# REV1.net
KiCad netlist of a schematic drawn in EAGLE
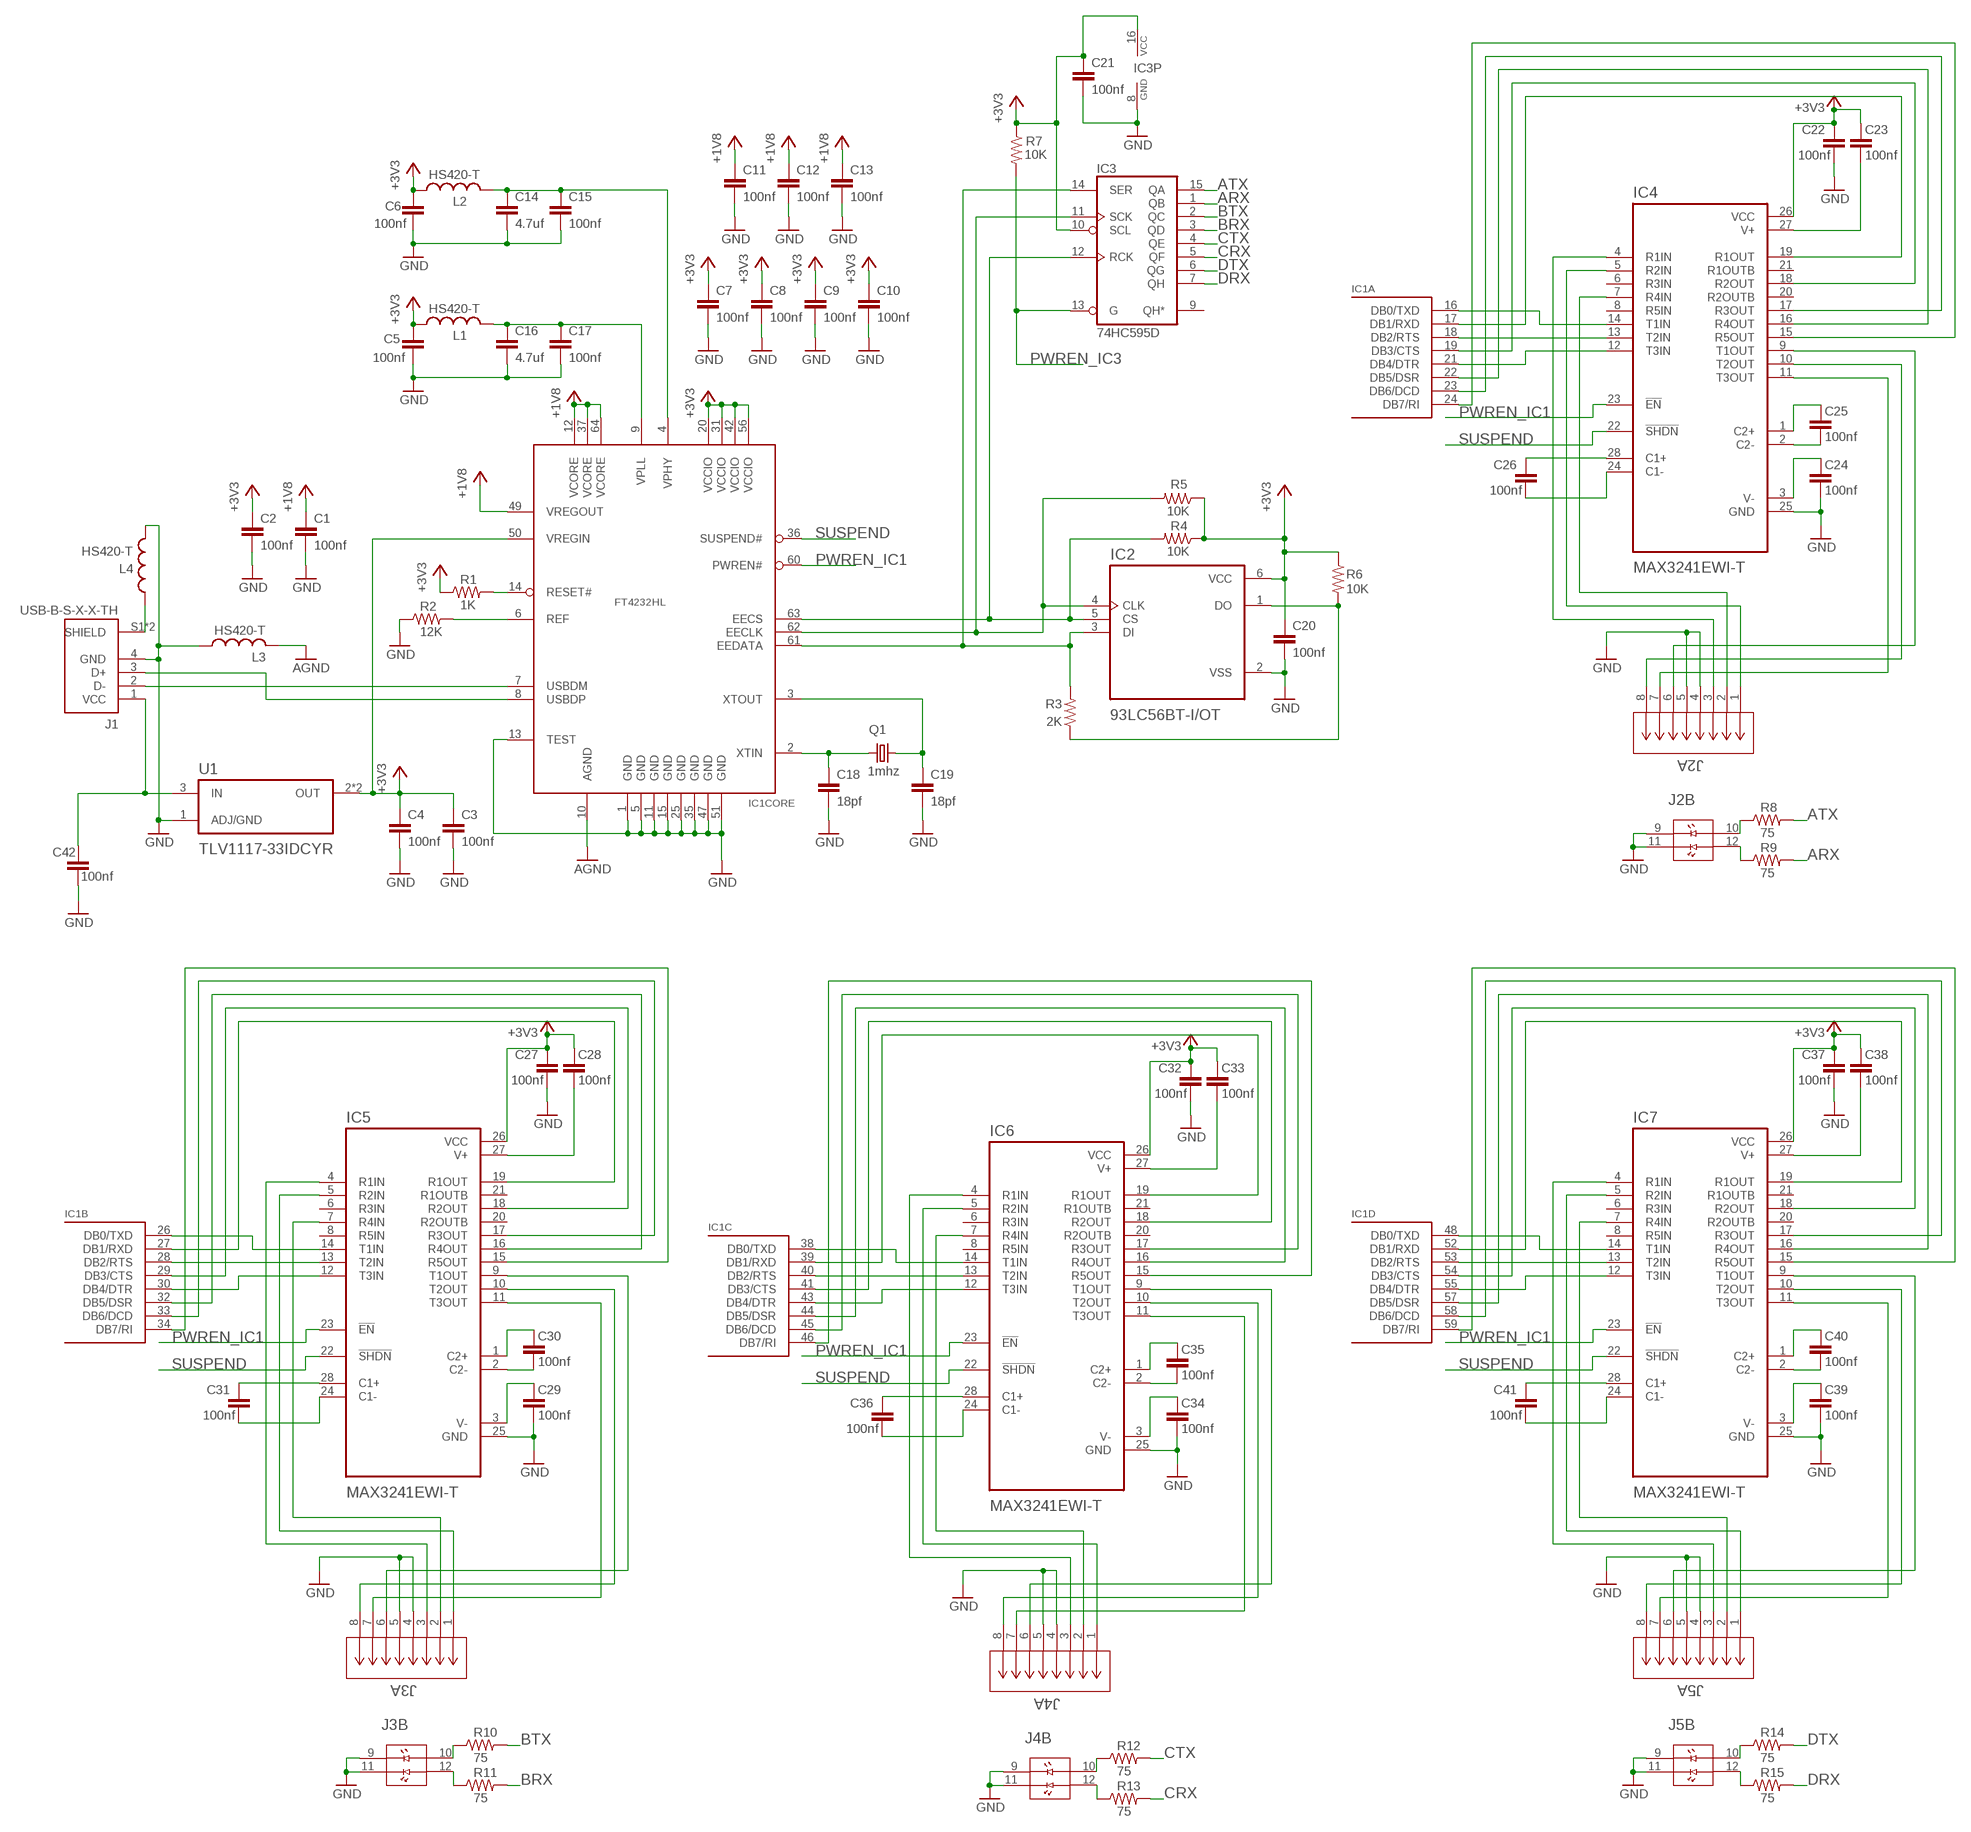
[diagram p0: schematic, sheet 1]

(export (version "E")
  (design (tool "Eeschema 10.0.6"))
  (components
    (comp (ref "C1")
      (value "100nf")
      (footprint "eagle-import:C0603")
      (libsource (lib "eagle-import") (part "C-EUC0603"))
    )
    (comp (ref "C2")
      (value "100nf")
      (footprint "eagle-import:C0603")
      (libsource (lib "eagle-import") (part "C-EUC0603"))
    )
    (comp (ref "C3")
      (value "100nf")
      (footprint "eagle-import:C0603")
      (libsource (lib "eagle-import") (part "C-EUC0603"))
    )
    (comp (ref "C4")
      (value "100nf")
      (footprint "eagle-import:C0603")
      (libsource (lib "eagle-import") (part "C-EUC0603"))
    )
    (comp (ref "C5")
      (value "100nf")
      (footprint "eagle-import:C0603")
      (libsource (lib "eagle-import") (part "C-EUC0603"))
    )
    (comp (ref "C6")
      (value "100nf")
      (footprint "eagle-import:C0603")
      (libsource (lib "eagle-import") (part "C-EUC0603"))
    )
    (comp (ref "C7")
      (value "100nf")
      (footprint "eagle-import:C0603")
      (libsource (lib "eagle-import") (part "C-EUC0603"))
    )
    (comp (ref "C8")
      (value "100nf")
      (footprint "eagle-import:C0603")
      (libsource (lib "eagle-import") (part "C-EUC0603"))
    )
    (comp (ref "C9")
      (value "100nf")
      (footprint "eagle-import:C0603")
      (libsource (lib "eagle-import") (part "C-EUC0603"))
    )
    (comp (ref "C10")
      (value "100nf")
      (footprint "eagle-import:C0603")
      (libsource (lib "eagle-import") (part "C-EUC0603"))
    )
    (comp (ref "C11")
      (value "100nf")
      (footprint "eagle-import:C0603")
      (libsource (lib "eagle-import") (part "C-EUC0603"))
    )
    (comp (ref "C12")
      (value "100nf")
      (footprint "eagle-import:C0603")
      (libsource (lib "eagle-import") (part "C-EUC0603"))
    )
    (comp (ref "C13")
      (value "100nf")
      (footprint "eagle-import:C0603")
      (libsource (lib "eagle-import") (part "C-EUC0603"))
    )
    (comp (ref "C14")
      (value "4.7uf")
      (footprint "eagle-import:C0603")
      (libsource (lib "eagle-import") (part "C-EUC0603"))
    )
    (comp (ref "C15")
      (value "100nf")
      (footprint "eagle-import:C0603")
      (libsource (lib "eagle-import") (part "C-EUC0603"))
    )
    (comp (ref "C16")
      (value "4.7uf")
      (footprint "eagle-import:C0603")
      (libsource (lib "eagle-import") (part "C-EUC0603"))
    )
    (comp (ref "C17")
      (value "100nf")
      (footprint "eagle-import:C0603")
      (libsource (lib "eagle-import") (part "C-EUC0603"))
    )
    (comp (ref "C18")
      (value "18pf")
      (footprint "eagle-import:C0603")
      (libsource (lib "eagle-import") (part "C-EUC0603"))
    )
    (comp (ref "C19")
      (value "18pf")
      (footprint "eagle-import:C0603")
      (libsource (lib "eagle-import") (part "C-EUC0603"))
    )
    (comp (ref "C20")
      (value "100nf")
      (footprint "eagle-import:C0603")
      (libsource (lib "eagle-import") (part "C-EUC0603"))
    )
    (comp (ref "C21")
      (value "100nf")
      (footprint "eagle-import:C0603")
      (libsource (lib "eagle-import") (part "C-EUC0603"))
    )
    (comp (ref "C22")
      (value "100nf")
      (footprint "eagle-import:C0603")
      (libsource (lib "eagle-import") (part "C-EUC0603"))
    )
    (comp (ref "C23")
      (value "100nf")
      (footprint "eagle-import:C0603")
      (libsource (lib "eagle-import") (part "C-EUC0603"))
    )
    (comp (ref "C24")
      (value "100nf")
      (footprint "eagle-import:C0603")
      (libsource (lib "eagle-import") (part "C-EUC0603"))
    )
    (comp (ref "C25")
      (value "100nf")
      (footprint "eagle-import:C0603")
      (libsource (lib "eagle-import") (part "C-EUC0603"))
    )
    (comp (ref "C26")
      (value "100nf")
      (footprint "eagle-import:C0603")
      (libsource (lib "eagle-import") (part "C-EUC0603"))
    )
    (comp (ref "C27")
      (value "100nf")
      (footprint "eagle-import:C0603")
      (libsource (lib "eagle-import") (part "C-EUC0603"))
    )
    (comp (ref "C28")
      (value "100nf")
      (footprint "eagle-import:C0603")
      (libsource (lib "eagle-import") (part "C-EUC0603"))
    )
    (comp (ref "C29")
      (value "100nf")
      (footprint "eagle-import:C0603")
      (libsource (lib "eagle-import") (part "C-EUC0603"))
    )
    (comp (ref "C30")
      (value "100nf")
      (footprint "eagle-import:C0603")
      (libsource (lib "eagle-import") (part "C-EUC0603"))
    )
    (comp (ref "C31")
      (value "100nf")
      (footprint "eagle-import:C0603")
      (libsource (lib "eagle-import") (part "C-EUC0603"))
    )
    (comp (ref "C32")
      (value "100nf")
      (footprint "eagle-import:C0603")
      (libsource (lib "eagle-import") (part "C-EUC0603"))
    )
    (comp (ref "C33")
      (value "100nf")
      (footprint "eagle-import:C0603")
      (libsource (lib "eagle-import") (part "C-EUC0603"))
    )
    (comp (ref "C34")
      (value "100nf")
      (footprint "eagle-import:C0603")
      (libsource (lib "eagle-import") (part "C-EUC0603"))
    )
    (comp (ref "C35")
      (value "100nf")
      (footprint "eagle-import:C0603")
      (libsource (lib "eagle-import") (part "C-EUC0603"))
    )
    (comp (ref "C36")
      (value "100nf")
      (footprint "eagle-import:C0603")
      (libsource (lib "eagle-import") (part "C-EUC0603"))
    )
    (comp (ref "C37")
      (value "100nf")
      (footprint "eagle-import:C0603")
      (libsource (lib "eagle-import") (part "C-EUC0603"))
    )
    (comp (ref "C38")
      (value "100nf")
      (footprint "eagle-import:C0603")
      (libsource (lib "eagle-import") (part "C-EUC0603"))
    )
    (comp (ref "C39")
      (value "100nf")
      (footprint "eagle-import:C0603")
      (libsource (lib "eagle-import") (part "C-EUC0603"))
    )
    (comp (ref "C40")
      (value "100nf")
      (footprint "eagle-import:C0603")
      (libsource (lib "eagle-import") (part "C-EUC0603"))
    )
    (comp (ref "C41")
      (value "100nf")
      (footprint "eagle-import:C0603")
      (libsource (lib "eagle-import") (part "C-EUC0603"))
    )
    (comp (ref "C42")
      (value "100nf")
      (footprint "eagle-import:C0603")
      (libsource (lib "eagle-import") (part "C-EUC0603"))
    )
    (comp (ref "IC1")
      (value "FT4232HL")
      (footprint "eagle-import:LQFP64")
      (libsource (lib "eagle-import") (part "FT4232HL"))
    )
    (comp (ref "IC2")
      (value "93LC56BT-I/OT")
      (footprint "eagle-import:SOT95P280X145-6N")
      (fields (field (name "MF") "Microchip Technology"))
      (libsource (lib "eagle-import") (part "93LC56BT-I/OT"))
    )
    (comp (ref "IC3")
      (value "74HC595D")
      (footprint "eagle-import:SO16")
      (libsource (lib "eagle-import") (part "74595DHC"))
    )
    (comp (ref "IC4")
      (value "MAX3241EWI-T")
      (footprint "eagle-import:SOIC127P1032X265-28N")
      (fields
        (field (name "DIGI-KEY_PART_NUMBER") "MAX3241EWI+T-ND")
        (field (name "MF") "Maxim Integrated")
        (field (name "MP") "MAX3241EWI+")
      )
      (libsource (lib "eagle-import") (part "MAX3241EWI-T"))
    )
    (comp (ref "IC5")
      (value "MAX3241EWI-T")
      (footprint "eagle-import:SOIC127P1032X265-28N")
      (fields
        (field (name "DIGI-KEY_PART_NUMBER") "MAX3241EWI+T-ND")
        (field (name "MF") "Maxim Integrated")
        (field (name "MP") "MAX3241EWI+")
      )
      (libsource (lib "eagle-import") (part "MAX3241EWI-T"))
    )
    (comp (ref "IC6")
      (value "MAX3241EWI-T")
      (footprint "eagle-import:SOIC127P1032X265-28N")
      (fields
        (field (name "DIGI-KEY_PART_NUMBER") "MAX3241EWI+T-ND")
        (field (name "MF") "Maxim Integrated")
        (field (name "MP") "MAX3241EWI+")
      )
      (libsource (lib "eagle-import") (part "MAX3241EWI-T"))
    )
    (comp (ref "IC7")
      (value "MAX3241EWI-T")
      (footprint "eagle-import:SOIC127P1032X265-28N")
      (fields
        (field (name "DIGI-KEY_PART_NUMBER") "MAX3241EWI+T-ND")
        (field (name "MF") "Maxim Integrated")
        (field (name "MP") "MAX3241EWI+")
      )
      (libsource (lib "eagle-import") (part "MAX3241EWI-T"))
    )
    (comp (ref "J1")
      (value "USB-B-S-X-X-TH")
      (footprint "eagle-import:SAMTEC_USB-B-S-X-X-TH")
      (fields (field (name "MF") "Samtec") (field (name "MP") "USB-B-S-S-B-TH"))
      (libsource (lib "eagle-import") (part "USB-B-S-X-X-TH"))
    )
    (comp (ref "J2")
      (value "RJHSE-5384")
      (footprint "eagle-import:RJHSE-5384_AMP")
      (fields (field (name "COPYRIGHT") "Copyright (C) 2018 Accelerated Designs. All rights reserved"))
      (libsource (lib "eagle-import") (part "RJHSE-5384"))
    )
    (comp (ref "J3")
      (value "RJHSE-5384")
      (footprint "eagle-import:RJHSE-5384_AMP")
      (fields (field (name "COPYRIGHT") "Copyright (C) 2018 Accelerated Designs. All rights reserved"))
      (libsource (lib "eagle-import") (part "RJHSE-5384"))
    )
    (comp (ref "J4")
      (value "RJHSE-5384")
      (footprint "eagle-import:RJHSE-5384_AMP")
      (fields (field (name "COPYRIGHT") "Copyright (C) 2018 Accelerated Designs. All rights reserved"))
      (libsource (lib "eagle-import") (part "RJHSE-5384"))
    )
    (comp (ref "J5")
      (value "RJHSE-5384")
      (footprint "eagle-import:RJHSE-5384_AMP")
      (fields (field (name "COPYRIGHT") "Copyright (C) 2018 Accelerated Designs. All rights reserved"))
      (libsource (lib "eagle-import") (part "RJHSE-5384"))
    )
    (comp (ref "L1")
      (value "HS420-T")
      (footprint "eagle-import:L2012C")
      (libsource (lib "eagle-import") (part "L-USL2012C"))
    )
    (comp (ref "L2")
      (value "HS420-T")
      (footprint "eagle-import:L2012C")
      (libsource (lib "eagle-import") (part "L-USL2012C"))
    )
    (comp (ref "L3")
      (value "HS420-T")
      (footprint "eagle-import:L2012C")
      (libsource (lib "eagle-import") (part "L-USL2012C"))
    )
    (comp (ref "L4")
      (value "HS420-T")
      (footprint "eagle-import:L2012C")
      (libsource (lib "eagle-import") (part "L-USL2012C"))
    )
    (comp (ref "Q1")
      (value "1mhz")
      (footprint "eagle-import:HC49_S")
      (libsource (lib "eagle-import") (part "CRYSTALHC49S"))
    )
    (comp (ref "R1")
      (value "1K")
      (footprint "eagle-import:R0805")
      (libsource (lib "eagle-import") (part "R-US_R0805"))
    )
    (comp (ref "R2")
      (value "12K")
      (footprint "eagle-import:R0805")
      (libsource (lib "eagle-import") (part "R-US_R0805"))
    )
    (comp (ref "R3")
      (value "2K")
      (footprint "eagle-import:R0805")
      (libsource (lib "eagle-import") (part "R-US_R0805"))
    )
    (comp (ref "R4")
      (value "10K")
      (footprint "eagle-import:R0805")
      (libsource (lib "eagle-import") (part "R-US_R0805"))
    )
    (comp (ref "R5")
      (value "10K")
      (footprint "eagle-import:R0805")
      (libsource (lib "eagle-import") (part "R-US_R0805"))
    )
    (comp (ref "R6")
      (value "10K")
      (footprint "eagle-import:R0805")
      (libsource (lib "eagle-import") (part "R-US_R0805"))
    )
    (comp (ref "R7")
      (value "10K")
      (footprint "eagle-import:R0805")
      (libsource (lib "eagle-import") (part "R-US_R0805"))
    )
    (comp (ref "R8")
      (value "75")
      (footprint "eagle-import:R0805")
      (libsource (lib "eagle-import") (part "R-US_R0805"))
    )
    (comp (ref "R9")
      (value "75")
      (footprint "eagle-import:R0805")
      (libsource (lib "eagle-import") (part "R-US_R0805"))
    )
    (comp (ref "R10")
      (value "75")
      (footprint "eagle-import:R0805")
      (libsource (lib "eagle-import") (part "R-US_R0805"))
    )
    (comp (ref "R11")
      (value "75")
      (footprint "eagle-import:R0805")
      (libsource (lib "eagle-import") (part "R-US_R0805"))
    )
    (comp (ref "R12")
      (value "75")
      (footprint "eagle-import:R0805")
      (libsource (lib "eagle-import") (part "R-US_R0805"))
    )
    (comp (ref "R13")
      (value "75")
      (footprint "eagle-import:R0805")
      (libsource (lib "eagle-import") (part "R-US_R0805"))
    )
    (comp (ref "R14")
      (value "75")
      (footprint "eagle-import:R0805")
      (libsource (lib "eagle-import") (part "R-US_R0805"))
    )
    (comp (ref "R15")
      (value "75")
      (footprint "eagle-import:R0805")
      (libsource (lib "eagle-import") (part "R-US_R0805"))
    )
    (comp (ref "U1")
      (value "TLV1117-33IDCYR")
      (footprint "eagle-import:SOT230P700X180-4N")
      (fields (field (name "DIGI-KEY_PART_NUMBER") "296-21113-1-ND") (field (name "MF") "Texas Instruments"))
      (libsource (lib "eagle-import") (part "TLV1117-33IDCYR"))
    )
  )
  (nets
    (net (code "1") (name "+1V8") (class "Default")
      (node (ref "C1") (pin "1") (pinfunction "1_1") (pintype "passive"))
      (node (ref "C11") (pin "1") (pinfunction "1_1") (pintype "passive"))
      (node (ref "C12") (pin "1") (pinfunction "1_1") (pintype "passive"))
      (node (ref "C13") (pin "1") (pinfunction "1_1") (pintype "passive"))
      (node (ref "IC1") (pin "12") (pinfunction "VCORE_12") (pintype "power_in"))
      (node (ref "IC1") (pin "37") (pinfunction "VCORE_37") (pintype "power_in"))
      (node (ref "IC1") (pin "49") (pinfunction "VREGOUT_49") (pintype "output"))
      (node (ref "IC1") (pin "64") (pinfunction "VCORE_64") (pintype "power_in"))
    )
    (net (code "2") (name "+3V3") (class "Default")
      (node (ref "C10") (pin "1") (pinfunction "1_1") (pintype "passive"))
      (node (ref "C2") (pin "1") (pinfunction "1_1") (pintype "passive"))
      (node (ref "C20") (pin "1") (pinfunction "1_1") (pintype "passive"))
      (node (ref "C21") (pin "1") (pinfunction "1_1") (pintype "passive"))
      (node (ref "C22") (pin "1") (pinfunction "1_1") (pintype "passive"))
      (node (ref "C23") (pin "1") (pinfunction "1_1") (pintype "passive"))
      (node (ref "C27") (pin "1") (pinfunction "1_1") (pintype "passive"))
      (node (ref "C28") (pin "1") (pinfunction "1_1") (pintype "passive"))
      (node (ref "C3") (pin "1") (pinfunction "1_1") (pintype "passive"))
      (node (ref "C32") (pin "1") (pinfunction "1_1") (pintype "passive"))
      (node (ref "C33") (pin "1") (pinfunction "1_1") (pintype "passive"))
      (node (ref "C37") (pin "1") (pinfunction "1_1") (pintype "passive"))
      (node (ref "C38") (pin "1") (pinfunction "1_1") (pintype "passive"))
      (node (ref "C4") (pin "1") (pinfunction "1_1") (pintype "passive"))
      (node (ref "C5") (pin "1") (pinfunction "1_1") (pintype "passive"))
      (node (ref "C6") (pin "1") (pinfunction "1_1") (pintype "passive"))
      (node (ref "C7") (pin "1") (pinfunction "1_1") (pintype "passive"))
      (node (ref "C8") (pin "1") (pinfunction "1_1") (pintype "passive"))
      (node (ref "C9") (pin "1") (pinfunction "1_1") (pintype "passive"))
      (node (ref "IC1") (pin "20") (pinfunction "VCCIO_20") (pintype "power_in"))
      (node (ref "IC1") (pin "31") (pinfunction "VCCIO_31") (pintype "power_in"))
      (node (ref "IC1") (pin "42") (pinfunction "VCCIO_42") (pintype "power_in"))
      (node (ref "IC1") (pin "50") (pinfunction "VREGIN_50") (pintype "bidirectional"))
      (node (ref "IC1") (pin "56") (pinfunction "VCCIO_56") (pintype "power_in"))
      (node (ref "IC2") (pin "6") (pinfunction "VCC_6") (pintype "power_in"))
      (node (ref "IC3") (pin "10") (pinfunction "SCL_10") (pintype "input"))
      (node (ref "IC3") (pin "16") (pinfunction "VCC_16") (pintype "power_in"))
      (node (ref "IC4") (pin "26") (pinfunction "VCC_26") (pintype "power_in"))
      (node (ref "IC5") (pin "26") (pinfunction "VCC_26") (pintype "power_in"))
      (node (ref "IC6") (pin "26") (pinfunction "VCC_26") (pintype "power_in"))
      (node (ref "IC7") (pin "26") (pinfunction "VCC_26") (pintype "power_in"))
      (node (ref "L1") (pin "1") (pinfunction "1_1") (pintype "passive"))
      (node (ref "L2") (pin "1") (pinfunction "1_1") (pintype "passive"))
      (node (ref "R1") (pin "1") (pinfunction "1_1") (pintype "passive"))
      (node (ref "R4") (pin "1") (pinfunction "1_1") (pintype "passive"))
      (node (ref "R5") (pin "1") (pinfunction "1_1") (pintype "passive"))
      (node (ref "R6") (pin "1") (pinfunction "1_1") (pintype "passive"))
      (node (ref "R7") (pin "1") (pinfunction "1_1") (pintype "passive"))
      (node (ref "U1") (pin "2") (pinfunction "OUT_2") (pintype "output"))
      (node (ref "U1") (pin "4") (pinfunction "OUT_4") (pintype "output"))
    )
    (net (code "3") (name "/ARX") (class "Default")
      (node (ref "IC3") (pin "1") (pinfunction "QB_1") (pintype "tri_state"))
      (node (ref "R9") (pin "2") (pinfunction "2_2") (pintype "passive"))
    )
    (net (code "4") (name "/ATX") (class "Default")
      (node (ref "IC3") (pin "15") (pinfunction "QA_15") (pintype "tri_state"))
      (node (ref "R8") (pin "2") (pinfunction "2_2") (pintype "passive"))
    )
    (net (code "5") (name "/BRX") (class "Default")
      (node (ref "IC3") (pin "3") (pinfunction "QD_3") (pintype "tri_state"))
      (node (ref "R11") (pin "2") (pinfunction "2_2") (pintype "passive"))
    )
    (net (code "6") (name "/BTX") (class "Default")
      (node (ref "IC3") (pin "2") (pinfunction "QC_2") (pintype "tri_state"))
      (node (ref "R10") (pin "2") (pinfunction "2_2") (pintype "passive"))
    )
    (net (code "7") (name "/CRX") (class "Default")
      (node (ref "IC3") (pin "5") (pinfunction "QF_5") (pintype "tri_state"))
      (node (ref "R13") (pin "2") (pinfunction "2_2") (pintype "passive"))
    )
    (net (code "8") (name "/CTX") (class "Default")
      (node (ref "IC3") (pin "4") (pinfunction "QE_4") (pintype "tri_state"))
      (node (ref "R12") (pin "2") (pinfunction "2_2") (pintype "passive"))
    )
    (net (code "9") (name "/DRX") (class "Default")
      (node (ref "IC3") (pin "7") (pinfunction "QH_7") (pintype "tri_state"))
      (node (ref "R15") (pin "2") (pinfunction "2_2") (pintype "passive"))
    )
    (net (code "10") (name "/DTX") (class "Default")
      (node (ref "IC3") (pin "6") (pinfunction "QG_6") (pintype "tri_state"))
      (node (ref "R14") (pin "2") (pinfunction "2_2") (pintype "passive"))
    )
    (net (code "11") (name "/PWREN_IC1") (class "Default")
      (node (ref "IC1") (pin "60") (pinfunction "PWREN#_60") (pintype "output"))
      (node (ref "IC4") (pin "23") (pinfunction "~{EN}_23") (pintype "bidirectional"))
      (node (ref "IC5") (pin "23") (pinfunction "~{EN}_23") (pintype "bidirectional"))
      (node (ref "IC6") (pin "23") (pinfunction "~{EN}_23") (pintype "bidirectional"))
      (node (ref "IC7") (pin "23") (pinfunction "~{EN}_23") (pintype "bidirectional"))
    )
    (net (code "12") (name "/PWREN_IC3") (class "Default")
      (node (ref "IC3") (pin "13") (pinfunction "G_13") (pintype "input"))
      (node (ref "R7") (pin "2") (pinfunction "2_2") (pintype "passive"))
    )
    (net (code "13") (name "/SUSPEND") (class "Default")
      (node (ref "IC1") (pin "36") (pinfunction "SUSPEND#_36") (pintype "output"))
      (node (ref "IC4") (pin "22") (pinfunction "~{SHDN}_22") (pintype "bidirectional"))
      (node (ref "IC5") (pin "22") (pinfunction "~{SHDN}_22") (pintype "bidirectional"))
      (node (ref "IC6") (pin "22") (pinfunction "~{SHDN}_22") (pintype "bidirectional"))
      (node (ref "IC7") (pin "22") (pinfunction "~{SHDN}_22") (pintype "bidirectional"))
    )
    (net (code "14") (name "AGND") (class "Default")
      (node (ref "IC1") (pin "10") (pinfunction "AGND_10") (pintype "power_in"))
      (node (ref "L3") (pin "2") (pinfunction "2_2") (pintype "passive"))
    )
    (net (code "15") (name "GND") (class "Default")
      (node (ref "C1") (pin "2") (pinfunction "2_2") (pintype "passive"))
      (node (ref "C10") (pin "2") (pinfunction "2_2") (pintype "passive"))
      (node (ref "C11") (pin "2") (pinfunction "2_2") (pintype "passive"))
      (node (ref "C12") (pin "2") (pinfunction "2_2") (pintype "passive"))
      (node (ref "C13") (pin "2") (pinfunction "2_2") (pintype "passive"))
      (node (ref "C14") (pin "2") (pinfunction "2_2") (pintype "passive"))
      (node (ref "C15") (pin "2") (pinfunction "2_2") (pintype "passive"))
      (node (ref "C16") (pin "2") (pinfunction "2_2") (pintype "passive"))
      (node (ref "C17") (pin "2") (pinfunction "2_2") (pintype "passive"))
      (node (ref "C18") (pin "2") (pinfunction "2_2") (pintype "passive"))
      (node (ref "C19") (pin "2") (pinfunction "2_2") (pintype "passive"))
      (node (ref "C2") (pin "2") (pinfunction "2_2") (pintype "passive"))
      (node (ref "C20") (pin "2") (pinfunction "2_2") (pintype "passive"))
      (node (ref "C21") (pin "2") (pinfunction "2_2") (pintype "passive"))
      (node (ref "C22") (pin "2") (pinfunction "2_2") (pintype "passive"))
      (node (ref "C24") (pin "2") (pinfunction "2_2") (pintype "passive"))
      (node (ref "C27") (pin "2") (pinfunction "2_2") (pintype "passive"))
      (node (ref "C29") (pin "2") (pinfunction "2_2") (pintype "passive"))
      (node (ref "C3") (pin "2") (pinfunction "2_2") (pintype "passive"))
      (node (ref "C32") (pin "2") (pinfunction "2_2") (pintype "passive"))
      (node (ref "C34") (pin "2") (pinfunction "2_2") (pintype "passive"))
      (node (ref "C37") (pin "2") (pinfunction "2_2") (pintype "passive"))
      (node (ref "C39") (pin "2") (pinfunction "2_2") (pintype "passive"))
      (node (ref "C4") (pin "2") (pinfunction "2_2") (pintype "passive"))
      (node (ref "C42") (pin "2") (pinfunction "2_2") (pintype "passive"))
      (node (ref "C5") (pin "2") (pinfunction "2_2") (pintype "passive"))
      (node (ref "C6") (pin "2") (pinfunction "2_2") (pintype "passive"))
      (node (ref "C7") (pin "2") (pinfunction "2_2") (pintype "passive"))
      (node (ref "C8") (pin "2") (pinfunction "2_2") (pintype "passive"))
      (node (ref "C9") (pin "2") (pinfunction "2_2") (pintype "passive"))
      (node (ref "IC1") (pin "1") (pinfunction "GND_1") (pintype "power_in"))
      (node (ref "IC1") (pin "11") (pinfunction "GND_11") (pintype "power_in"))
      (node (ref "IC1") (pin "13") (pinfunction "TEST_13") (pintype "input"))
      (node (ref "IC1") (pin "15") (pinfunction "GND_15") (pintype "power_in"))
      (node (ref "IC1") (pin "25") (pinfunction "GND_25") (pintype "power_in"))
      (node (ref "IC1") (pin "35") (pinfunction "GND_35") (pintype "power_in"))
      (node (ref "IC1") (pin "47") (pinfunction "GND_47") (pintype "power_in"))
      (node (ref "IC1") (pin "5") (pinfunction "GND_5") (pintype "power_in"))
      (node (ref "IC1") (pin "51") (pinfunction "GND_51") (pintype "power_in"))
      (node (ref "IC2") (pin "2") (pinfunction "VSS_2") (pintype "power_in"))
      (node (ref "IC3") (pin "8") (pinfunction "GND_8") (pintype "power_in"))
      (node (ref "IC4") (pin "25") (pinfunction "GND_25") (pintype "power_in"))
      (node (ref "IC5") (pin "25") (pinfunction "GND_25") (pintype "power_in"))
      (node (ref "IC6") (pin "25") (pinfunction "GND_25") (pintype "power_in"))
      (node (ref "IC7") (pin "25") (pinfunction "GND_25") (pintype "power_in"))
      (node (ref "J1") (pin "4") (pinfunction "GND_4") (pintype "power_in"))
      (node (ref "J2") (pin "11") (pinfunction "11_11") (pintype "passive"))
      (node (ref "J2") (pin "4") (pinfunction "4_4") (pintype "passive"))
      (node (ref "J2") (pin "5") (pinfunction "5_5") (pintype "passive"))
      (node (ref "J2") (pin "9") (pinfunction "9_9") (pintype "passive"))
      (node (ref "J3") (pin "11") (pinfunction "11_11") (pintype "passive"))
      (node (ref "J3") (pin "4") (pinfunction "4_4") (pintype "passive"))
      (node (ref "J3") (pin "5") (pinfunction "5_5") (pintype "passive"))
      (node (ref "J3") (pin "9") (pinfunction "9_9") (pintype "passive"))
      (node (ref "J4") (pin "11") (pinfunction "11_11") (pintype "passive"))
      (node (ref "J4") (pin "4") (pinfunction "4_4") (pintype "passive"))
      (node (ref "J4") (pin "5") (pinfunction "5_5") (pintype "passive"))
      (node (ref "J4") (pin "9") (pinfunction "9_9") (pintype "passive"))
      (node (ref "J5") (pin "11") (pinfunction "11_11") (pintype "passive"))
      (node (ref "J5") (pin "4") (pinfunction "4_4") (pintype "passive"))
      (node (ref "J5") (pin "5") (pinfunction "5_5") (pintype "passive"))
      (node (ref "J5") (pin "9") (pinfunction "9_9") (pintype "passive"))
      (node (ref "L3") (pin "1") (pinfunction "1_1") (pintype "passive"))
      (node (ref "L4") (pin "2") (pinfunction "2_2") (pintype "passive"))
      (node (ref "R2") (pin "1") (pinfunction "1_1") (pintype "passive"))
      (node (ref "U1") (pin "1") (pinfunction "ADJ/GND_1") (pintype "bidirectional"))
    )
    (net (code "16") (name "Net-(IC1A-DB0{slash}TXD)") (class "Default")
      (node (ref "IC1") (pin "16") (pinfunction "DB0/TXD_16") (pintype "bidirectional"))
      (node (ref "IC4") (pin "14") (pinfunction "T1IN_14") (pintype "input"))
    )
    (net (code "17") (name "Net-(IC1A-DB1{slash}RXD)") (class "Default")
      (node (ref "IC1") (pin "17") (pinfunction "DB1/RXD_17") (pintype "bidirectional"))
      (node (ref "IC4") (pin "19") (pinfunction "R1OUT_19") (pintype "output"))
    )
    (net (code "18") (name "Net-(IC1A-DB2{slash}RTS)") (class "Default")
      (node (ref "IC1") (pin "18") (pinfunction "DB2/RTS_18") (pintype "bidirectional"))
      (node (ref "IC4") (pin "13") (pinfunction "T2IN_13") (pintype "input"))
    )
    (net (code "19") (name "Net-(IC1A-DB3{slash}CTS)") (class "Default")
      (node (ref "IC1") (pin "19") (pinfunction "DB3/CTS_19") (pintype "bidirectional"))
      (node (ref "IC4") (pin "18") (pinfunction "R2OUT_18") (pintype "output"))
    )
    (net (code "20") (name "Net-(IC1A-DB4{slash}DTR)") (class "Default")
      (node (ref "IC1") (pin "21") (pinfunction "DB4/DTR_21") (pintype "bidirectional"))
      (node (ref "IC4") (pin "12") (pinfunction "T3IN_12") (pintype "input"))
    )
    (net (code "21") (name "Net-(IC1A-DB5{slash}DSR)") (class "Default")
      (node (ref "IC1") (pin "22") (pinfunction "DB5/DSR_22") (pintype "bidirectional"))
      (node (ref "IC4") (pin "16") (pinfunction "R4OUT_16") (pintype "output"))
    )
    (net (code "22") (name "Net-(IC1A-DB6{slash}DCD)") (class "Default")
      (node (ref "IC1") (pin "23") (pinfunction "DB6/DCD_23") (pintype "bidirectional"))
      (node (ref "IC4") (pin "17") (pinfunction "R3OUT_17") (pintype "output"))
    )
    (net (code "23") (name "Net-(IC1A-DB7{slash}RI)") (class "Default")
      (node (ref "IC1") (pin "24") (pinfunction "DB7/RI_24") (pintype "bidirectional"))
      (node (ref "IC4") (pin "15") (pinfunction "R5OUT_15") (pintype "output"))
    )
    (net (code "24") (name "Net-(IC1B-DB0{slash}TXD)") (class "Default")
      (node (ref "IC1") (pin "26") (pinfunction "DB0/TXD_26") (pintype "bidirectional"))
      (node (ref "IC5") (pin "14") (pinfunction "T1IN_14") (pintype "input"))
    )
    (net (code "25") (name "Net-(IC1B-DB1{slash}RXD)") (class "Default")
      (node (ref "IC1") (pin "27") (pinfunction "DB1/RXD_27") (pintype "bidirectional"))
      (node (ref "IC5") (pin "19") (pinfunction "R1OUT_19") (pintype "output"))
    )
    (net (code "26") (name "Net-(IC1B-DB2{slash}RTS)") (class "Default")
      (node (ref "IC1") (pin "28") (pinfunction "DB2/RTS_28") (pintype "bidirectional"))
      (node (ref "IC5") (pin "13") (pinfunction "T2IN_13") (pintype "input"))
    )
    (net (code "27") (name "Net-(IC1B-DB3{slash}CTS)") (class "Default")
      (node (ref "IC1") (pin "29") (pinfunction "DB3/CTS_29") (pintype "bidirectional"))
      (node (ref "IC5") (pin "18") (pinfunction "R2OUT_18") (pintype "output"))
    )
    (net (code "28") (name "Net-(IC1B-DB4{slash}DTR)") (class "Default")
      (node (ref "IC1") (pin "30") (pinfunction "DB4/DTR_30") (pintype "bidirectional"))
      (node (ref "IC5") (pin "12") (pinfunction "T3IN_12") (pintype "input"))
    )
    (net (code "29") (name "Net-(IC1B-DB5{slash}DSR)") (class "Default")
      (node (ref "IC1") (pin "32") (pinfunction "DB5/DSR_32") (pintype "bidirectional"))
      (node (ref "IC5") (pin "16") (pinfunction "R4OUT_16") (pintype "output"))
    )
    (net (code "30") (name "Net-(IC1B-DB6{slash}DCD)") (class "Default")
      (node (ref "IC1") (pin "33") (pinfunction "DB6/DCD_33") (pintype "bidirectional"))
      (node (ref "IC5") (pin "17") (pinfunction "R3OUT_17") (pintype "output"))
    )
    (net (code "31") (name "Net-(IC1B-DB7{slash}RI)") (class "Default")
      (node (ref "IC1") (pin "34") (pinfunction "DB7/RI_34") (pintype "bidirectional"))
      (node (ref "IC5") (pin "15") (pinfunction "R5OUT_15") (pintype "output"))
    )
    (net (code "32") (name "Net-(IC1C-DB0{slash}TXD)") (class "Default")
      (node (ref "IC1") (pin "38") (pinfunction "DB0/TXD_38") (pintype "bidirectional"))
      (node (ref "IC6") (pin "14") (pinfunction "T1IN_14") (pintype "input"))
    )
    (net (code "33") (name "Net-(IC1C-DB1{slash}RXD)") (class "Default")
      (node (ref "IC1") (pin "39") (pinfunction "DB1/RXD_39") (pintype "bidirectional"))
      (node (ref "IC6") (pin "19") (pinfunction "R1OUT_19") (pintype "output"))
    )
    (net (code "34") (name "Net-(IC1C-DB2{slash}RTS)") (class "Default")
      (node (ref "IC1") (pin "40") (pinfunction "DB2/RTS_40") (pintype "bidirectional"))
      (node (ref "IC6") (pin "13") (pinfunction "T2IN_13") (pintype "input"))
    )
    (net (code "35") (name "Net-(IC1C-DB3{slash}CTS)") (class "Default")
      (node (ref "IC1") (pin "41") (pinfunction "DB3/CTS_41") (pintype "bidirectional"))
      (node (ref "IC6") (pin "18") (pinfunction "R2OUT_18") (pintype "output"))
    )
    (net (code "36") (name "Net-(IC1C-DB4{slash}DTR)") (class "Default")
      (node (ref "IC1") (pin "43") (pinfunction "DB4/DTR_43") (pintype "bidirectional"))
      (node (ref "IC6") (pin "12") (pinfunction "T3IN_12") (pintype "input"))
    )
    (net (code "37") (name "Net-(IC1C-DB5{slash}DSR)") (class "Default")
      (node (ref "IC1") (pin "44") (pinfunction "DB5/DSR_44") (pintype "bidirectional"))
      (node (ref "IC6") (pin "16") (pinfunction "R4OUT_16") (pintype "output"))
    )
    (net (code "38") (name "Net-(IC1C-DB6{slash}DCD)") (class "Default")
      (node (ref "IC1") (pin "45") (pinfunction "DB6/DCD_45") (pintype "bidirectional"))
      (node (ref "IC6") (pin "17") (pinfunction "R3OUT_17") (pintype "output"))
    )
    (net (code "39") (name "Net-(IC1C-DB7{slash}RI)") (class "Default")
      (node (ref "IC1") (pin "46") (pinfunction "DB7/RI_46") (pintype "bidirectional"))
      (node (ref "IC6") (pin "15") (pinfunction "R5OUT_15") (pintype "output"))
    )
    (net (code "40") (name "Net-(IC1D-EECLK)") (class "Default")
      (node (ref "IC1") (pin "62") (pinfunction "EECLK_62") (pintype "output"))
      (node (ref "IC2") (pin "4") (pinfunction "CLK_4") (pintype "input"))
      (node (ref "IC3") (pin "11") (pinfunction "SCK_11") (pintype "input"))
      (node (ref "R5") (pin "2") (pinfunction "2_2") (pintype "passive"))
    )
    (net (code "41") (name "Net-(IC1D-EECS)") (class "Default")
      (node (ref "IC1") (pin "63") (pinfunction "EECS_63") (pintype "bidirectional"))
      (node (ref "IC2") (pin "5") (pinfunction "CS_5") (pintype "input"))
      (node (ref "IC3") (pin "12") (pinfunction "RCK_12") (pintype "input"))
      (node (ref "R4") (pin "2") (pinfunction "2_2") (pintype "passive"))
    )
    (net (code "42") (name "Net-(IC1D-EEDATA)") (class "Default")
      (node (ref "IC1") (pin "61") (pinfunction "EEDATA_61") (pintype "bidirectional"))
      (node (ref "IC2") (pin "3") (pinfunction "DI_3") (pintype "input"))
      (node (ref "IC3") (pin "14") (pinfunction "SER_14") (pintype "input"))
      (node (ref "R3") (pin "2") (pinfunction "2_2") (pintype "passive"))
    )
    (net (code "43") (name "Net-(IC1D-REF)") (class "Default")
      (node (ref "IC1") (pin "6") (pinfunction "REF_6") (pintype "input"))
      (node (ref "R2") (pin "2") (pinfunction "2_2") (pintype "passive"))
    )
    (net (code "44") (name "Net-(IC1D-RESET#)") (class "Default")
      (node (ref "IC1") (pin "14") (pinfunction "RESET#_14") (pintype "input"))
      (node (ref "R1") (pin "2") (pinfunction "2_2") (pintype "passive"))
    )
    (net (code "45") (name "Net-(IC1D-USBDM)") (class "Default")
      (node (ref "IC1") (pin "7") (pinfunction "USBDM_7") (pintype "input"))
      (node (ref "J1") (pin "2") (pinfunction "D-_2") (pintype "bidirectional"))
    )
    (net (code "46") (name "Net-(IC1D-USBDP)") (class "Default")
      (node (ref "IC1") (pin "8") (pinfunction "USBDP_8") (pintype "input"))
      (node (ref "J1") (pin "3") (pinfunction "D+_3") (pintype "bidirectional"))
    )
    (net (code "47") (name "Net-(IC1D-VPHY)") (class "Default")
      (node (ref "C14") (pin "1") (pinfunction "1_1") (pintype "passive"))
      (node (ref "C15") (pin "1") (pinfunction "1_1") (pintype "passive"))
      (node (ref "IC1") (pin "4") (pinfunction "VPHY_4") (pintype "power_in"))
      (node (ref "L2") (pin "2") (pinfunction "2_2") (pintype "passive"))
    )
    (net (code "48") (name "Net-(IC1D-VPLL)") (class "Default")
      (node (ref "C16") (pin "1") (pinfunction "1_1") (pintype "passive"))
      (node (ref "C17") (pin "1") (pinfunction "1_1") (pintype "passive"))
      (node (ref "IC1") (pin "9") (pinfunction "VPLL_9") (pintype "power_in"))
      (node (ref "L1") (pin "2") (pinfunction "2_2") (pintype "passive"))
    )
    (net (code "49") (name "Net-(IC1D-XTIN)") (class "Default")
      (node (ref "C18") (pin "1") (pinfunction "1_1") (pintype "passive"))
      (node (ref "IC1") (pin "2") (pinfunction "XTIN_2") (pintype "input"))
      (node (ref "Q1") (pin "2") (pinfunction "2_2") (pintype "passive"))
    )
    (net (code "50") (name "Net-(IC1D-XTOUT)") (class "Default")
      (node (ref "C19") (pin "1") (pinfunction "1_1") (pintype "passive"))
      (node (ref "IC1") (pin "3") (pinfunction "XTOUT_3") (pintype "output"))
      (node (ref "Q1") (pin "1") (pinfunction "1_1") (pintype "passive"))
    )
    (net (code "51") (name "Net-(IC1E-DB0{slash}TXD)") (class "Default")
      (node (ref "IC1") (pin "48") (pinfunction "DB0/TXD_48") (pintype "bidirectional"))
      (node (ref "IC7") (pin "14") (pinfunction "T1IN_14") (pintype "input"))
    )
    (net (code "52") (name "Net-(IC1E-DB1{slash}RXD)") (class "Default")
      (node (ref "IC1") (pin "52") (pinfunction "DB1/RXD_52") (pintype "bidirectional"))
      (node (ref "IC7") (pin "19") (pinfunction "R1OUT_19") (pintype "output"))
    )
    (net (code "53") (name "Net-(IC1E-DB2{slash}RTS)") (class "Default")
      (node (ref "IC1") (pin "53") (pinfunction "DB2/RTS_53") (pintype "bidirectional"))
      (node (ref "IC7") (pin "13") (pinfunction "T2IN_13") (pintype "input"))
    )
    (net (code "54") (name "Net-(IC1E-DB3{slash}CTS)") (class "Default")
      (node (ref "IC1") (pin "54") (pinfunction "DB3/CTS_54") (pintype "bidirectional"))
      (node (ref "IC7") (pin "18") (pinfunction "R2OUT_18") (pintype "output"))
    )
    (net (code "55") (name "Net-(IC1E-DB4{slash}DTR)") (class "Default")
      (node (ref "IC1") (pin "55") (pinfunction "DB4/DTR_55") (pintype "bidirectional"))
      (node (ref "IC7") (pin "12") (pinfunction "T3IN_12") (pintype "input"))
    )
    (net (code "56") (name "Net-(IC1E-DB5{slash}DSR)") (class "Default")
      (node (ref "IC1") (pin "57") (pinfunction "DB5/DSR_57") (pintype "bidirectional"))
      (node (ref "IC7") (pin "16") (pinfunction "R4OUT_16") (pintype "output"))
    )
    (net (code "57") (name "Net-(IC1E-DB6{slash}DCD)") (class "Default")
      (node (ref "IC1") (pin "58") (pinfunction "DB6/DCD_58") (pintype "bidirectional"))
      (node (ref "IC7") (pin "17") (pinfunction "R3OUT_17") (pintype "output"))
    )
    (net (code "58") (name "Net-(IC1E-DB7{slash}RI)") (class "Default")
      (node (ref "IC1") (pin "59") (pinfunction "DB7/RI_59") (pintype "bidirectional"))
      (node (ref "IC7") (pin "15") (pinfunction "R5OUT_15") (pintype "output"))
    )
    (net (code "59") (name "Net-(IC2-DO)") (class "Default")
      (node (ref "IC2") (pin "1") (pinfunction "DO_1") (pintype "output"))
      (node (ref "R3") (pin "1") (pinfunction "1_1") (pintype "passive"))
      (node (ref "R6") (pin "2") (pinfunction "2_2") (pintype "passive"))
    )
    (net (code "60") (name "Net-(IC4-C1+)") (class "Default")
      (node (ref "C26") (pin "1") (pinfunction "1_1") (pintype "passive"))
      (node (ref "IC4") (pin "28") (pinfunction "C1+_28") (pintype "bidirectional"))
    )
    (net (code "61") (name "Net-(IC4-C1-)") (class "Default")
      (node (ref "C26") (pin "2") (pinfunction "2_2") (pintype "passive"))
      (node (ref "IC4") (pin "24") (pinfunction "C1-_24") (pintype "bidirectional"))
    )
    (net (code "62") (name "Net-(IC4-C2+)") (class "Default")
      (node (ref "C25") (pin "1") (pinfunction "1_1") (pintype "passive"))
      (node (ref "IC4") (pin "1") (pinfunction "C2+_1") (pintype "bidirectional"))
    )
    (net (code "63") (name "Net-(IC4-C2-)") (class "Default")
      (node (ref "C25") (pin "2") (pinfunction "2_2") (pintype "passive"))
      (node (ref "IC4") (pin "2") (pinfunction "C2-_2") (pintype "bidirectional"))
    )
    (net (code "64") (name "Net-(IC4-R1IN)") (class "Default")
      (node (ref "IC4") (pin "4") (pinfunction "R1IN_4") (pintype "input"))
      (node (ref "J2") (pin "3") (pinfunction "3_3") (pintype "passive"))
    )
    (net (code "65") (name "Net-(IC4-R2IN)") (class "Default")
      (node (ref "IC4") (pin "5") (pinfunction "R2IN_5") (pintype "input"))
      (node (ref "J2") (pin "1") (pinfunction "1_1") (pintype "passive"))
    )
    (net (code "66") (name "Net-(IC4-R4IN)") (class "Default")
      (node (ref "IC4") (pin "7") (pinfunction "R4IN_7") (pintype "input"))
      (node (ref "J2") (pin "2") (pinfunction "2_2") (pintype "passive"))
    )
    (net (code "67") (name "Net-(IC4-T1OUT)") (class "Default")
      (node (ref "IC4") (pin "9") (pinfunction "T1OUT_9") (pintype "output"))
      (node (ref "J2") (pin "6") (pinfunction "6_6") (pintype "passive"))
    )
    (net (code "68") (name "Net-(IC4-T2OUT)") (class "Default")
      (node (ref "IC4") (pin "10") (pinfunction "T2OUT_10") (pintype "output"))
      (node (ref "J2") (pin "8") (pinfunction "8_8") (pintype "passive"))
    )
    (net (code "69") (name "Net-(IC4-T3OUT)") (class "Default")
      (node (ref "IC4") (pin "11") (pinfunction "T3OUT_11") (pintype "output"))
      (node (ref "J2") (pin "7") (pinfunction "7_7") (pintype "passive"))
    )
    (net (code "70") (name "Net-(IC4-V+)") (class "Default")
      (node (ref "C23") (pin "2") (pinfunction "2_2") (pintype "passive"))
      (node (ref "IC4") (pin "27") (pinfunction "V+_27") (pintype "power_in"))
    )
    (net (code "71") (name "Net-(IC4-V-)") (class "Default")
      (node (ref "C24") (pin "1") (pinfunction "1_1") (pintype "passive"))
      (node (ref "IC4") (pin "3") (pinfunction "V-_3") (pintype "power_in"))
    )
    (net (code "72") (name "Net-(IC5-C1+)") (class "Default")
      (node (ref "C31") (pin "1") (pinfunction "1_1") (pintype "passive"))
      (node (ref "IC5") (pin "28") (pinfunction "C1+_28") (pintype "bidirectional"))
    )
    (net (code "73") (name "Net-(IC5-C1-)") (class "Default")
      (node (ref "C31") (pin "2") (pinfunction "2_2") (pintype "passive"))
      (node (ref "IC5") (pin "24") (pinfunction "C1-_24") (pintype "bidirectional"))
    )
    (net (code "74") (name "Net-(IC5-C2+)") (class "Default")
      (node (ref "C30") (pin "1") (pinfunction "1_1") (pintype "passive"))
      (node (ref "IC5") (pin "1") (pinfunction "C2+_1") (pintype "bidirectional"))
    )
    (net (code "75") (name "Net-(IC5-C2-)") (class "Default")
      (node (ref "C30") (pin "2") (pinfunction "2_2") (pintype "passive"))
      (node (ref "IC5") (pin "2") (pinfunction "C2-_2") (pintype "bidirectional"))
    )
    (net (code "76") (name "Net-(IC5-R1IN)") (class "Default")
      (node (ref "IC5") (pin "4") (pinfunction "R1IN_4") (pintype "input"))
      (node (ref "J3") (pin "3") (pinfunction "3_3") (pintype "passive"))
    )
    (net (code "77") (name "Net-(IC5-R2IN)") (class "Default")
      (node (ref "IC5") (pin "5") (pinfunction "R2IN_5") (pintype "input"))
      (node (ref "J3") (pin "1") (pinfunction "1_1") (pintype "passive"))
    )
    (net (code "78") (name "Net-(IC5-R4IN)") (class "Default")
      (node (ref "IC5") (pin "7") (pinfunction "R4IN_7") (pintype "input"))
      (node (ref "J3") (pin "2") (pinfunction "2_2") (pintype "passive"))
    )
    (net (code "79") (name "Net-(IC5-T1OUT)") (class "Default")
      (node (ref "IC5") (pin "9") (pinfunction "T1OUT_9") (pintype "output"))
      (node (ref "J3") (pin "6") (pinfunction "6_6") (pintype "passive"))
    )
    (net (code "80") (name "Net-(IC5-T2OUT)") (class "Default")
      (node (ref "IC5") (pin "10") (pinfunction "T2OUT_10") (pintype "output"))
      (node (ref "J3") (pin "8") (pinfunction "8_8") (pintype "passive"))
    )
    (net (code "81") (name "Net-(IC5-T3OUT)") (class "Default")
      (node (ref "IC5") (pin "11") (pinfunction "T3OUT_11") (pintype "output"))
      (node (ref "J3") (pin "7") (pinfunction "7_7") (pintype "passive"))
    )
    (net (code "82") (name "Net-(IC5-V+)") (class "Default")
      (node (ref "C28") (pin "2") (pinfunction "2_2") (pintype "passive"))
      (node (ref "IC5") (pin "27") (pinfunction "V+_27") (pintype "power_in"))
    )
    (net (code "83") (name "Net-(IC5-V-)") (class "Default")
      (node (ref "C29") (pin "1") (pinfunction "1_1") (pintype "passive"))
      (node (ref "IC5") (pin "3") (pinfunction "V-_3") (pintype "power_in"))
    )
    (net (code "84") (name "Net-(IC6-C1+)") (class "Default")
      (node (ref "C36") (pin "1") (pinfunction "1_1") (pintype "passive"))
      (node (ref "IC6") (pin "28") (pinfunction "C1+_28") (pintype "bidirectional"))
    )
    (net (code "85") (name "Net-(IC6-C1-)") (class "Default")
      (node (ref "C36") (pin "2") (pinfunction "2_2") (pintype "passive"))
      (node (ref "IC6") (pin "24") (pinfunction "C1-_24") (pintype "bidirectional"))
    )
    (net (code "86") (name "Net-(IC6-C2+)") (class "Default")
      (node (ref "C35") (pin "1") (pinfunction "1_1") (pintype "passive"))
      (node (ref "IC6") (pin "1") (pinfunction "C2+_1") (pintype "bidirectional"))
    )
    (net (code "87") (name "Net-(IC6-C2-)") (class "Default")
      (node (ref "C35") (pin "2") (pinfunction "2_2") (pintype "passive"))
      (node (ref "IC6") (pin "2") (pinfunction "C2-_2") (pintype "bidirectional"))
    )
    (net (code "88") (name "Net-(IC6-R1IN)") (class "Default")
      (node (ref "IC6") (pin "4") (pinfunction "R1IN_4") (pintype "input"))
      (node (ref "J4") (pin "3") (pinfunction "3_3") (pintype "passive"))
    )
    (net (code "89") (name "Net-(IC6-R2IN)") (class "Default")
      (node (ref "IC6") (pin "5") (pinfunction "R2IN_5") (pintype "input"))
      (node (ref "J4") (pin "1") (pinfunction "1_1") (pintype "passive"))
    )
    (net (code "90") (name "Net-(IC6-R4IN)") (class "Default")
      (node (ref "IC6") (pin "7") (pinfunction "R4IN_7") (pintype "input"))
      (node (ref "J4") (pin "2") (pinfunction "2_2") (pintype "passive"))
    )
    (net (code "91") (name "Net-(IC6-T1OUT)") (class "Default")
      (node (ref "IC6") (pin "9") (pinfunction "T1OUT_9") (pintype "output"))
      (node (ref "J4") (pin "6") (pinfunction "6_6") (pintype "passive"))
    )
    (net (code "92") (name "Net-(IC6-T2OUT)") (class "Default")
      (node (ref "IC6") (pin "10") (pinfunction "T2OUT_10") (pintype "output"))
      (node (ref "J4") (pin "8") (pinfunction "8_8") (pintype "passive"))
    )
    (net (code "93") (name "Net-(IC6-T3OUT)") (class "Default")
      (node (ref "IC6") (pin "11") (pinfunction "T3OUT_11") (pintype "output"))
      (node (ref "J4") (pin "7") (pinfunction "7_7") (pintype "passive"))
    )
    (net (code "94") (name "Net-(IC6-V+)") (class "Default")
      (node (ref "C33") (pin "2") (pinfunction "2_2") (pintype "passive"))
      (node (ref "IC6") (pin "27") (pinfunction "V+_27") (pintype "power_in"))
    )
    (net (code "95") (name "Net-(IC6-V-)") (class "Default")
      (node (ref "C34") (pin "1") (pinfunction "1_1") (pintype "passive"))
      (node (ref "IC6") (pin "3") (pinfunction "V-_3") (pintype "power_in"))
    )
    (net (code "96") (name "Net-(IC7-C1+)") (class "Default")
      (node (ref "C41") (pin "1") (pinfunction "1_1") (pintype "passive"))
      (node (ref "IC7") (pin "28") (pinfunction "C1+_28") (pintype "bidirectional"))
    )
    (net (code "97") (name "Net-(IC7-C1-)") (class "Default")
      (node (ref "C41") (pin "2") (pinfunction "2_2") (pintype "passive"))
      (node (ref "IC7") (pin "24") (pinfunction "C1-_24") (pintype "bidirectional"))
    )
    (net (code "98") (name "Net-(IC7-C2+)") (class "Default")
      (node (ref "C40") (pin "1") (pinfunction "1_1") (pintype "passive"))
      (node (ref "IC7") (pin "1") (pinfunction "C2+_1") (pintype "bidirectional"))
    )
    (net (code "99") (name "Net-(IC7-C2-)") (class "Default")
      (node (ref "C40") (pin "2") (pinfunction "2_2") (pintype "passive"))
      (node (ref "IC7") (pin "2") (pinfunction "C2-_2") (pintype "bidirectional"))
    )
    (net (code "100") (name "Net-(IC7-R1IN)") (class "Default")
      (node (ref "IC7") (pin "4") (pinfunction "R1IN_4") (pintype "input"))
      (node (ref "J5") (pin "3") (pinfunction "3_3") (pintype "passive"))
    )
    (net (code "101") (name "Net-(IC7-R2IN)") (class "Default")
      (node (ref "IC7") (pin "5") (pinfunction "R2IN_5") (pintype "input"))
      (node (ref "J5") (pin "1") (pinfunction "1_1") (pintype "passive"))
    )
    (net (code "102") (name "Net-(IC7-R4IN)") (class "Default")
      (node (ref "IC7") (pin "7") (pinfunction "R4IN_7") (pintype "input"))
      (node (ref "J5") (pin "2") (pinfunction "2_2") (pintype "passive"))
    )
    (net (code "103") (name "Net-(IC7-T1OUT)") (class "Default")
      (node (ref "IC7") (pin "9") (pinfunction "T1OUT_9") (pintype "output"))
      (node (ref "J5") (pin "6") (pinfunction "6_6") (pintype "passive"))
    )
    (net (code "104") (name "Net-(IC7-T2OUT)") (class "Default")
      (node (ref "IC7") (pin "10") (pinfunction "T2OUT_10") (pintype "output"))
      (node (ref "J5") (pin "8") (pinfunction "8_8") (pintype "passive"))
    )
    (net (code "105") (name "Net-(IC7-T3OUT)") (class "Default")
      (node (ref "IC7") (pin "11") (pinfunction "T3OUT_11") (pintype "output"))
      (node (ref "J5") (pin "7") (pinfunction "7_7") (pintype "passive"))
    )
    (net (code "106") (name "Net-(IC7-V+)") (class "Default")
      (node (ref "C38") (pin "2") (pinfunction "2_2") (pintype "passive"))
      (node (ref "IC7") (pin "27") (pinfunction "V+_27") (pintype "power_in"))
    )
    (net (code "107") (name "Net-(IC7-V-)") (class "Default")
      (node (ref "C39") (pin "1") (pinfunction "1_1") (pintype "passive"))
      (node (ref "IC7") (pin "3") (pinfunction "V-_3") (pintype "power_in"))
    )
    (net (code "108") (name "Net-(J1-SHIELD-PadS1)") (class "Default")
      (node (ref "J1") (pin "S1") (pinfunction "SHIELD_S1") (pintype "passive"))
      (node (ref "J1") (pin "S2") (pinfunction "SHIELD_S2") (pintype "passive"))
      (node (ref "L4") (pin "1") (pinfunction "1_1") (pintype "passive"))
    )
    (net (code "109") (name "Net-(J1-VCC)") (class "Default")
      (node (ref "C42") (pin "1") (pinfunction "1_1") (pintype "passive"))
      (node (ref "J1") (pin "1") (pinfunction "VCC_1") (pintype "power_in"))
      (node (ref "U1") (pin "3") (pinfunction "IN_3") (pintype "input"))
    )
    (net (code "110") (name "Net-(J2-Pad10)") (class "Default")
      (node (ref "J2") (pin "10") (pinfunction "10_10") (pintype "passive"))
      (node (ref "R8") (pin "1") (pinfunction "1_1") (pintype "passive"))
    )
    (net (code "111") (name "Net-(J2-Pad12)") (class "Default")
      (node (ref "J2") (pin "12") (pinfunction "12_12") (pintype "passive"))
      (node (ref "R9") (pin "1") (pinfunction "1_1") (pintype "passive"))
    )
    (net (code "112") (name "Net-(J3-Pad10)") (class "Default")
      (node (ref "J3") (pin "10") (pinfunction "10_10") (pintype "passive"))
      (node (ref "R10") (pin "1") (pinfunction "1_1") (pintype "passive"))
    )
    (net (code "113") (name "Net-(J3-Pad12)") (class "Default")
      (node (ref "J3") (pin "12") (pinfunction "12_12") (pintype "passive"))
      (node (ref "R11") (pin "1") (pinfunction "1_1") (pintype "passive"))
    )
    (net (code "114") (name "Net-(J4-Pad10)") (class "Default")
      (node (ref "J4") (pin "10") (pinfunction "10_10") (pintype "passive"))
      (node (ref "R12") (pin "1") (pinfunction "1_1") (pintype "passive"))
    )
    (net (code "115") (name "Net-(J4-Pad12)") (class "Default")
      (node (ref "J4") (pin "12") (pinfunction "12_12") (pintype "passive"))
      (node (ref "R13") (pin "1") (pinfunction "1_1") (pintype "passive"))
    )
    (net (code "116") (name "Net-(J5-Pad10)") (class "Default")
      (node (ref "J5") (pin "10") (pinfunction "10_10") (pintype "passive"))
      (node (ref "R14") (pin "1") (pinfunction "1_1") (pintype "passive"))
    )
    (net (code "117") (name "Net-(J5-Pad12)") (class "Default")
      (node (ref "J5") (pin "12") (pinfunction "12_12") (pintype "passive"))
      (node (ref "R15") (pin "1") (pinfunction "1_1") (pintype "passive"))
    )
    (net (code "118") (name "unconnected-(IC3A-QH*-Pad9)") (class "Default")
      (node (ref "IC3") (pin "9") (pinfunction "QH*_9") (pintype "tri_state"))
    )
    (net (code "119") (name "unconnected-(IC4-R1OUTB-Pad21)") (class "Default")
      (node (ref "IC4") (pin "21") (pinfunction "R1OUTB_21") (pintype "output"))
    )
    (net (code "120") (name "unconnected-(IC4-R2OUTB-Pad20)") (class "Default")
      (node (ref "IC4") (pin "20") (pinfunction "R2OUTB_20") (pintype "output"))
    )
    (net (code "121") (name "unconnected-(IC4-R3IN-Pad6)") (class "Default")
      (node (ref "IC4") (pin "6") (pinfunction "R3IN_6") (pintype "input"))
    )
    (net (code "122") (name "unconnected-(IC4-R5IN-Pad8)") (class "Default")
      (node (ref "IC4") (pin "8") (pinfunction "R5IN_8") (pintype "input"))
    )
    (net (code "123") (name "unconnected-(IC5-R1OUTB-Pad21)") (class "Default")
      (node (ref "IC5") (pin "21") (pinfunction "R1OUTB_21") (pintype "output"))
    )
    (net (code "124") (name "unconnected-(IC5-R2OUTB-Pad20)") (class "Default")
      (node (ref "IC5") (pin "20") (pinfunction "R2OUTB_20") (pintype "output"))
    )
    (net (code "125") (name "unconnected-(IC5-R3IN-Pad6)") (class "Default")
      (node (ref "IC5") (pin "6") (pinfunction "R3IN_6") (pintype "input"))
    )
    (net (code "126") (name "unconnected-(IC5-R5IN-Pad8)") (class "Default")
      (node (ref "IC5") (pin "8") (pinfunction "R5IN_8") (pintype "input"))
    )
    (net (code "127") (name "unconnected-(IC6-R1OUTB-Pad21)") (class "Default")
      (node (ref "IC6") (pin "21") (pinfunction "R1OUTB_21") (pintype "output"))
    )
    (net (code "128") (name "unconnected-(IC6-R2OUTB-Pad20)") (class "Default")
      (node (ref "IC6") (pin "20") (pinfunction "R2OUTB_20") (pintype "output"))
    )
    (net (code "129") (name "unconnected-(IC6-R3IN-Pad6)") (class "Default")
      (node (ref "IC6") (pin "6") (pinfunction "R3IN_6") (pintype "input"))
    )
    (net (code "130") (name "unconnected-(IC6-R5IN-Pad8)") (class "Default")
      (node (ref "IC6") (pin "8") (pinfunction "R5IN_8") (pintype "input"))
    )
    (net (code "131") (name "unconnected-(IC7-R1OUTB-Pad21)") (class "Default")
      (node (ref "IC7") (pin "21") (pinfunction "R1OUTB_21") (pintype "output"))
    )
    (net (code "132") (name "unconnected-(IC7-R2OUTB-Pad20)") (class "Default")
      (node (ref "IC7") (pin "20") (pinfunction "R2OUTB_20") (pintype "output"))
    )
    (net (code "133") (name "unconnected-(IC7-R3IN-Pad6)") (class "Default")
      (node (ref "IC7") (pin "6") (pinfunction "R3IN_6") (pintype "input"))
    )
    (net (code "134") (name "unconnected-(IC7-R5IN-Pad8)") (class "Default")
      (node (ref "IC7") (pin "8") (pinfunction "R5IN_8") (pintype "input"))
    )
  )
)
